# jetson_nano_breakout_rev1.net
KiCad netlist of a schematic drawn in Altium Designer
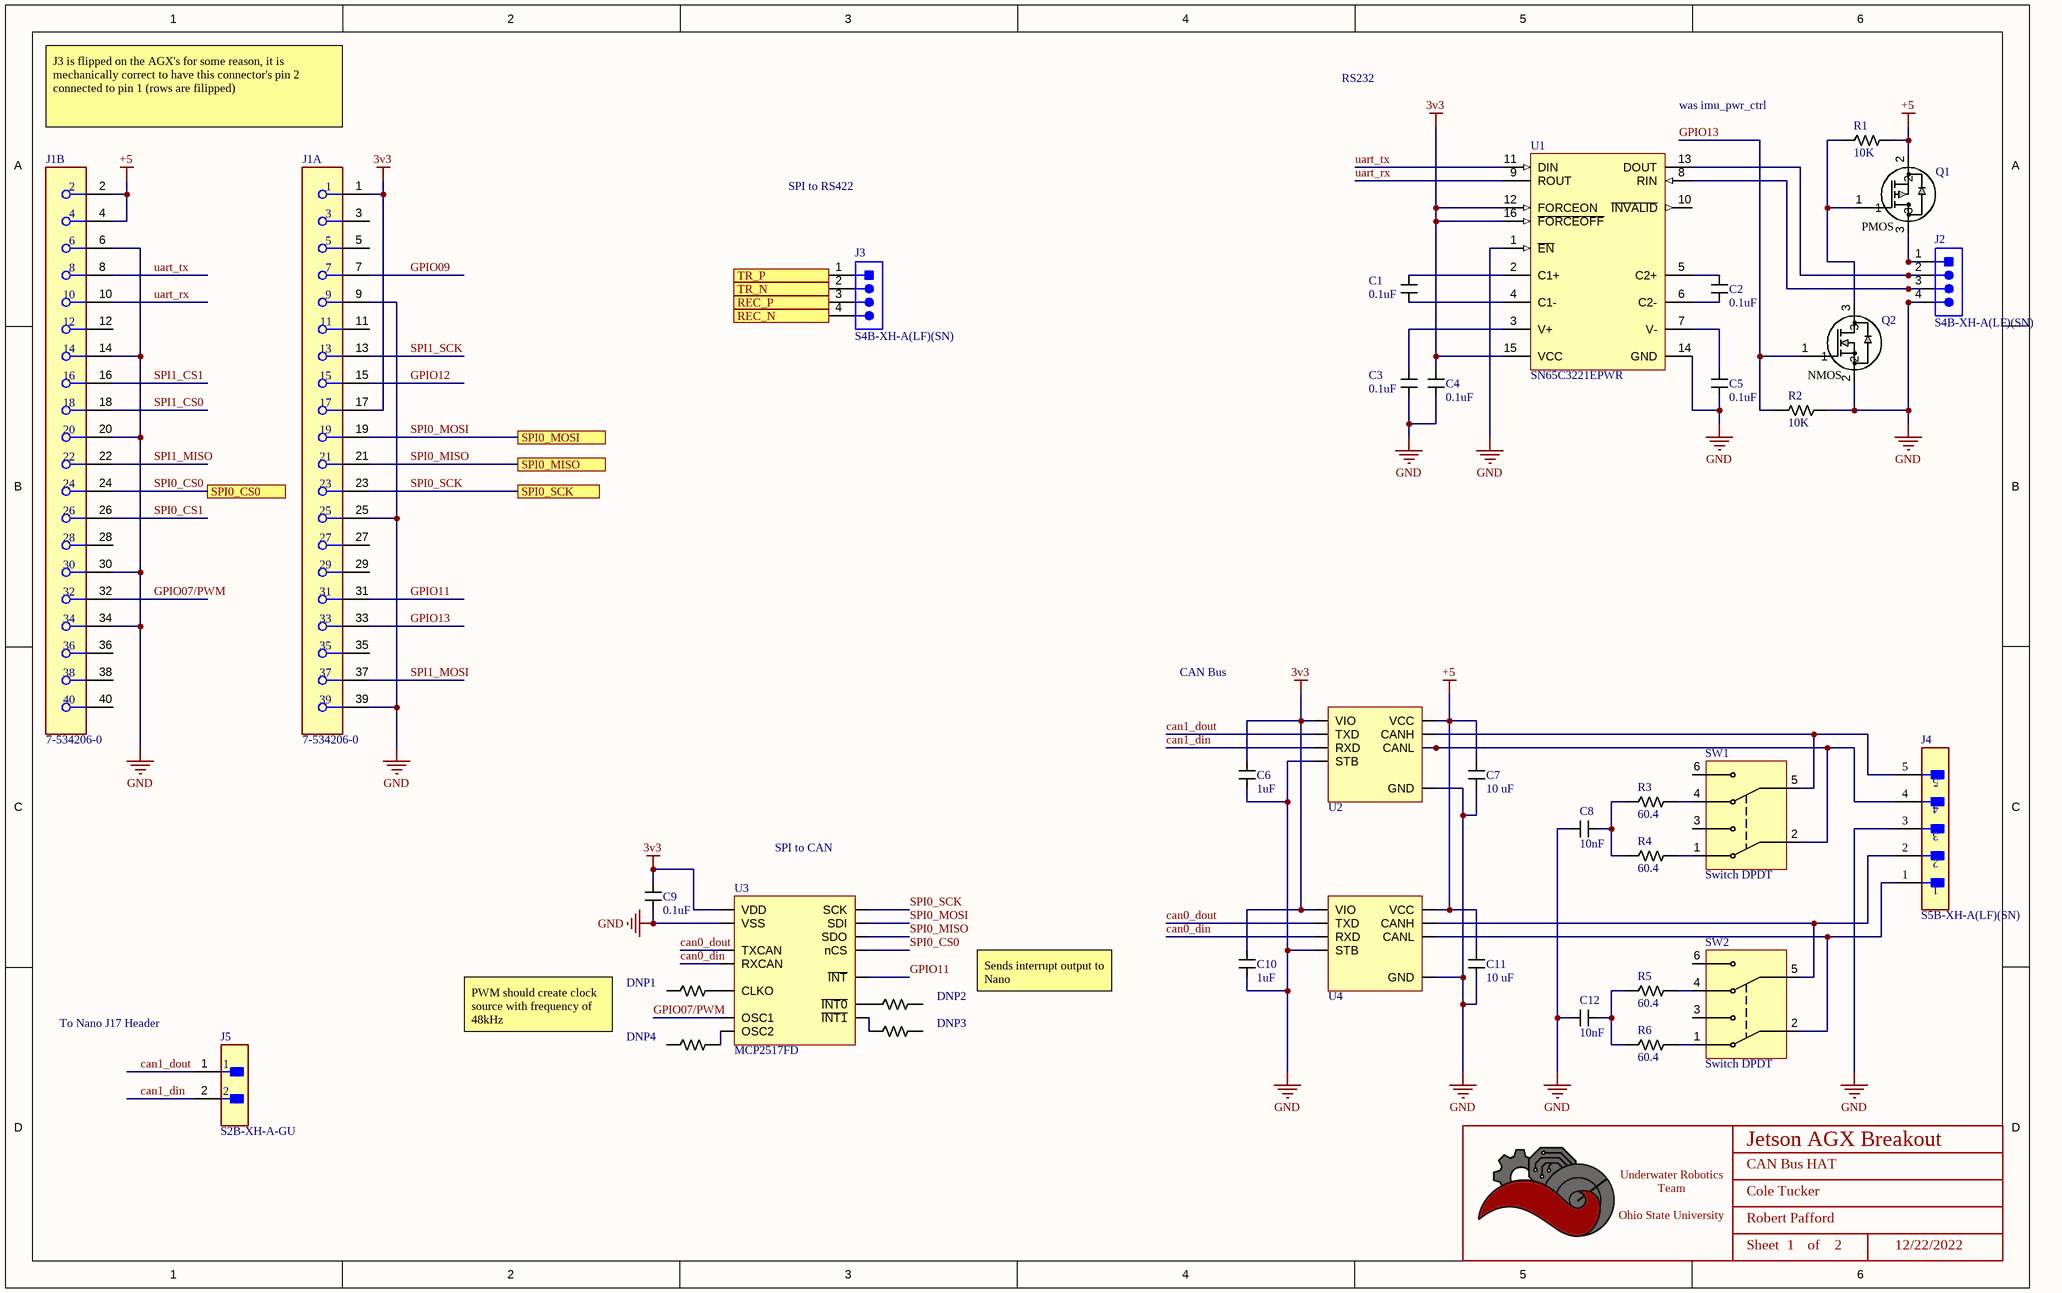
[diagram p0: jetson_nano_breakout_rev1.SchDoc]

(export (version "E")
  (design (tool "Eeschema 10.0.6"))
  (components
    (comp (ref "C1")
      (value "0.1uF")
      (footprint "CAPACITOR_0603")
      (description "Cap 100nF 6.3V +/-10%\r\nCeramic 0603")
      (fields
        (field (name "TOLERANCE") "+/- 10%")
        (field (name "VOLTAGE") "6.3V")
        (field (name "MADE BY") "Flip B")
      )
      (libsource (lib "Capacitors") (part "CAPACITOR_0.1uF_0603"))
    )
    (comp (ref "C2")
      (value "0.1uF")
      (footprint "CAPACITOR_0603")
      (description "Cap 100nF 6.3V +/-10%\r\nCeramic 0603")
      (fields
        (field (name "TOLERANCE") "+/- 10%")
        (field (name "VOLTAGE") "6.3V")
        (field (name "MADE BY") "Flip B")
      )
      (libsource (lib "Capacitors") (part "CAPACITOR_0.1uF_0603"))
    )
    (comp (ref "C3")
      (value "0.1uF")
      (footprint "CAPACITOR_0603")
      (description "Cap 100nF 6.3V +/-10%\r\nCeramic 0603")
      (fields
        (field (name "TOLERANCE") "+/- 10%")
        (field (name "VOLTAGE") "6.3V")
        (field (name "MADE BY") "Flip B")
      )
      (libsource (lib "Capacitors") (part "CAPACITOR_0.1uF_0603"))
    )
    (comp (ref "C4")
      (value "0.1uF")
      (footprint "CAPACITOR_0603")
      (description "Cap 100nF 6.3V +/-10%\r\nCeramic 0603")
      (fields
        (field (name "TOLERANCE") "+/- 10%")
        (field (name "VOLTAGE") "6.3V")
        (field (name "MADE BY") "Flip B")
      )
      (libsource (lib "Capacitors") (part "CAPACITOR_0.1uF_0603"))
    )
    (comp (ref "C5")
      (value "0.1uF")
      (footprint "CAPACITOR_0603")
      (description "Cap 100nF 6.3V +/-10%\r\nCeramic 0603")
      (fields
        (field (name "TOLERANCE") "+/- 10%")
        (field (name "VOLTAGE") "6.3V")
        (field (name "MADE BY") "Flip B")
      )
      (libsource (lib "Capacitors") (part "CAPACITOR_0.1uF_0603"))
    )
    (comp (ref "C6")
      (value "1uF")
      (footprint "CAPACITOR_0603")
      (description "Cap 1uF 16V +/-10%\r\nCeramic 0603")
      (fields
        (field (name "TOLERANCE") "+/- 10%")
        (field (name "VOLTAGE") "16V")
        (field (name "MADE BY") "Flip B")
      )
      (libsource (lib "Capacitors") (part "CAPACITOR_1uF_0603"))
    )
    (comp (ref "C7")
      (value "10uF Ceramic 6.3V")
      (footprint "CAPACITOR_0603")
      (description "Cap 10uF 6.3V +/-20%\r\nCeramic 0603")
      (fields
        (field (name "TOLERANCE") "+/- 20%")
        (field (name "VOLTAGE") "6.3V")
        (field (name "VALUE (UF)") "10 uF")
        (field (name "MADE BY") "Flip B")
      )
      (libsource (lib "Capacitors") (part "CAPACITOR_10uF_0603"))
    )
    (comp (ref "C8")
      (value "10nF")
      (footprint "CAPACITOR_0603")
      (description "Cap 10nF 6.3V +/-20%\r\nCeramic 0603")
      (fields
        (field (name "TOLERANCE") "+/- 10%")
        (field (name "VOLTAGE") "6.3V")
        (field (name "MADE BY") "Flip B")
      )
      (libsource (lib "Capacitors") (part "CAPACITOR_0.01uF_0603"))
    )
    (comp (ref "C9")
      (value "0.1uF")
      (footprint "CAPACITOR_0402")
      (description "Cap 100nF 25V +/-10%\r\nCeramic 0402")
      (fields
        (field (name "TOLERANCE") "+/- 10%")
        (field (name "VOLTAGE") "25V")
        (field (name "MADE BY") "Robert Pafford")
      )
      (libsource (lib "Capacitors") (part "CAPACITOR_0.1uF_0402"))
    )
    (comp (ref "C10")
      (value "1uF")
      (footprint "CAPACITOR_0603")
      (description "Cap 1uF 16V +/-10%\r\nCeramic 0603")
      (fields
        (field (name "TOLERANCE") "+/- 10%")
        (field (name "VOLTAGE") "16V")
        (field (name "MADE BY") "Flip B")
      )
      (libsource (lib "Capacitors") (part "CAPACITOR_1uF_0603"))
    )
    (comp (ref "C11")
      (value "10uF Ceramic 6.3V")
      (footprint "CAPACITOR_0603")
      (description "Cap 10uF 6.3V +/-20%\r\nCeramic 0603")
      (fields
        (field (name "TOLERANCE") "+/- 20%")
        (field (name "VOLTAGE") "6.3V")
        (field (name "VALUE (UF)") "10 uF")
        (field (name "MADE BY") "Flip B")
      )
      (libsource (lib "Capacitors") (part "CAPACITOR_10uF_0603"))
    )
    (comp (ref "C12")
      (value "10nF")
      (footprint "CAPACITOR_0603")
      (description "Cap 10nF 6.3V +/-20%\r\nCeramic 0603")
      (fields
        (field (name "TOLERANCE") "+/- 10%")
        (field (name "VOLTAGE") "6.3V")
        (field (name "MADE BY") "Flip B")
      )
      (libsource (lib "Capacitors") (part "CAPACITOR_0.01uF_0603"))
    )
    (comp (ref "DNP1")
      (value "DNP")
      (footprint "RESISTOR_0402")
      (description "Do Not Populate 0402")
      (libsource (lib "Resistors") (part "DNP_0402"))
    )
    (comp (ref "DNP2")
      (value "DNP")
      (footprint "RESISTOR_0402")
      (description "Do Not Populate 0402")
      (libsource (lib "Resistors") (part "DNP_0402"))
    )
    (comp (ref "DNP3")
      (value "DNP")
      (footprint "RESISTOR_0402")
      (description "Do Not Populate 0402")
      (libsource (lib "Resistors") (part "DNP_0402"))
    )
    (comp (ref "DNP4")
      (value "DNP")
      (footprint "RESISTOR_0402")
      (description "Do Not Populate 0402")
      (libsource (lib "Resistors") (part "DNP_0402"))
    )
    (comp (ref "J1")
      (value "7-534206-0")
      (footprint "FP-7-534206-0-MFG")
      (description "CONN RCPT 40POS 0.1 GOLD PCB")
      (fields
        (field (name "MANUFACTURER") "TE Connectivity")
        (field (name "OCTOPART") "https://octopart.com/7-534206-0-te+connectivity-39516831")
      )
      (libsource (lib "Altium Content Vault") (part "7acf1c4a8db21028d11741a46a6ec78"))
    )
    (comp (ref "J2")
      (value "S4B-XH-A(LF)(SN)")
      (footprint "JST-S4B-XH-A(LF)(SN)_V")
      (libsource (lib "Altium Content Vault") (part "CN-1P-M-R4"))
    )
    (comp (ref "J3")
      (value "S4B-XH-A(LF)(SN)")
      (footprint "JST-S4B-XH-A(LF)(SN)_V")
      (libsource (lib "Altium Content Vault") (part "CN-1P-M-R4"))
    )
    (comp (ref "J4")
      (value "S5B-XH-A(LF)(SN)")
      (footprint "FP-S5B-XH-A_LF_SN-MFG")
      (description "CONN HEADER R/A 5POS 2.5MM")
      (libsource (lib "Altium Content Vault") (part "bf93c07fd2649a848d0ec8585582aab"))
    )
    (comp (ref "J5")
      (value "S2B-XH-A-GU")
      (footprint "FP-S2B-XH-A-GU-MFG")
      (description "Conn Shrouded Header HDR 2 POS 2.45mm Solder ST Top Entry Thru-Hole")
      (libsource (lib "Altium Content Vault") (part "3bc925449376181038e59eaffc5286c"))
    )
    (comp (ref "Q1")
      (value "MOSFET P-CHANNEL 20V 4.7A SOT23")
      (footprint "SOT-23-3")
      (description "P-Channel 20 V 4.7A (Tc) 1.56W (Tc) Surface Mount SOT-23")
      (fields
        (field (name "MANUFACTURER_PART_NUMBER") "TSM500P02CX")
        (field (name "CREATED BY") "Robert Pafford")
      )
      (libsource (lib "Transistors") (part "TSM500P02CX"))
    )
    (comp (ref "Q2")
      (value "MOSFET N-CH 30V 5.8A SOT-23-3")
      (footprint "SOT-23-3")
      (description "N-Channel 30 V 5.8A (Ta) 1.4W (Ta) Surface Mount SOT-23-3")
      (fields (field (name "MANUFACTURER _PART_NUMBER") "AO3404A") (field (name "CREATED BY") "Dylan T"))
      (libsource (lib "Transistors") (part "AO3404A"))
    )
    (comp (ref "R1")
      (value "10k Ohm 5% 1/10W")
      (footprint "RESISTOR_0603")
      (description "RES 10k OHM 5% 1/10W 0603")
      (fields
        (field (name "TOLERANCE") "+/- 5%")
        (field (name "VALUE  (OHMS)") "10K")
        (field (name "MADE BY") "Robert Pafford")
      )
      (libsource (lib "Resistors") (part "RESISTOR_10K_0603"))
    )
    (comp (ref "R2")
      (value "10k Ohm 5% 1/10W")
      (footprint "RESISTOR_0603")
      (description "RES 10k OHM 5% 1/10W 0603")
      (fields
        (field (name "TOLERANCE") "+/- 5%")
        (field (name "VALUE  (OHMS)") "10K")
        (field (name "MADE BY") "Robert Pafford")
      )
      (libsource (lib "Resistors") (part "RESISTOR_10K_0603"))
    )
    (comp (ref "R3")
      (value "60.4 Ohm 1% 1/16W")
      (footprint "RESISTOR_0402")
      (description "RES 60.4 OHM 1% 1/16W 0402")
      (fields
        (field (name "TOLERANCE") "+/- 1%")
        (field (name "VALUE  (OHMS)") "60.4")
        (field (name "MADE BY") "Robert Pafford")
      )
      (libsource (lib "Resistors") (part "RESISTOR_60.4_0402"))
    )
    (comp (ref "R4")
      (value "60.4 Ohm 1% 1/16W")
      (footprint "RESISTOR_0402")
      (description "RES 60.4 OHM 1% 1/16W 0402")
      (fields
        (field (name "TOLERANCE") "+/- 1%")
        (field (name "VALUE  (OHMS)") "60.4")
        (field (name "MADE BY") "Robert Pafford")
      )
      (libsource (lib "Resistors") (part "RESISTOR_60.4_0402"))
    )
    (comp (ref "R5")
      (value "60.4 Ohm 1% 1/16W")
      (footprint "RESISTOR_0402")
      (description "RES 60.4 OHM 1% 1/16W 0402")
      (fields
        (field (name "TOLERANCE") "+/- 1%")
        (field (name "VALUE  (OHMS)") "60.4")
        (field (name "MADE BY") "Robert Pafford")
      )
      (libsource (lib "Resistors") (part "RESISTOR_60.4_0402"))
    )
    (comp (ref "R6")
      (value "60.4 Ohm 1% 1/16W")
      (footprint "RESISTOR_0402")
      (description "RES 60.4 OHM 1% 1/16W 0402")
      (fields
        (field (name "TOLERANCE") "+/- 1%")
        (field (name "VALUE  (OHMS)") "60.4")
        (field (name "MADE BY") "Robert Pafford")
      )
      (libsource (lib "Resistors") (part "RESISTOR_60.4_0402"))
    )
    (comp (ref "SW1")
      (value "Switch DPDT")
      (footprint "CAS-220TA")
      (description "GOLD SWITCH FLUSH SLIDE DPDT 100MA 6V")
      (fields (field (name "MADE BY") "Robert Pafford"))
      (libsource (lib "Switches") (part "CAS-220TA_CAN_TERM"))
    )
    (comp (ref "SW2")
      (value "Switch DPDT")
      (footprint "CAS-220TA")
      (description "GOLD SWITCH FLUSH SLIDE DPDT 100MA 6V")
      (fields (field (name "MADE BY") "Robert Pafford"))
      (libsource (lib "Switches") (part "CAS-220TA_CAN_TERM"))
    )
    (comp (ref "U1")
      (value "SN65C3221EPWR")
      (footprint "PW0016A_M")
      (libsource (lib "Altium Content Vault") (part "TI-SN65C3221E-TSSOP_PW-16"))
    )
    (comp (ref "U2")
      (value "CAN Transceiver")
      (footprint "SOIC-8")
      (description "CAN Interface IC High-Speed CAN Transceiver with Standby Mode")
      (fields (field (name "MADE BY") "Robert Pafford"))
      (libsource (lib "Integrated Circuits") (part "TJA1442AT"))
    )
    (comp (ref "U3")
      (value "MCP2517FD")
      (footprint "SOIC-14")
      (description "CANbus Controller CAN 2.0 SPI Interface 14-SOIC")
      (fields (field (name "MADE BY") "Robert Pafford"))
      (libsource (lib "Integrated Circuits") (part "MCP2517FD"))
    )
    (comp (ref "U4")
      (value "CAN Transceiver")
      (footprint "SOIC-8")
      (description "CAN Interface IC High-Speed CAN Transceiver with Standby Mode")
      (fields (field (name "MADE BY") "Robert Pafford"))
      (libsource (lib "Integrated Circuits") (part "TJA1442AT"))
    )
  )
  (nets
    (net (code "1") (name "+5") (class "Default")
      (node (ref "C11") (pin "1") (pinfunction "1_1") (pintype "passive"))
      (node (ref "C7") (pin "1") (pinfunction "1_1") (pintype "passive"))
      (node (ref "J1") (pin "2") (pinfunction "2_2") (pintype "passive"))
      (node (ref "J1") (pin "4") (pinfunction "4_4") (pintype "passive"))
      (node (ref "Q1") (pin "2") (pinfunction "2_2") (pintype "passive"))
      (node (ref "R1") (pin "1") (pinfunction "1_1") (pintype "passive"))
      (node (ref "U2") (pin "3") (pinfunction "VCC_3") (pintype "passive"))
      (node (ref "U4") (pin "3") (pinfunction "VCC_3") (pintype "passive"))
    )
    (net (code "2") (name "/GPIO07{slash}PWM") (class "Default")
      (node (ref "J1") (pin "32") (pinfunction "32_32") (pintype "passive"))
      (node (ref "U3") (pin "6") (pinfunction "OSC1_6") (pintype "passive"))
    )
    (net (code "3") (name "/GPIO09") (class "Default")
      (node (ref "J1") (pin "7") (pinfunction "7_7") (pintype "passive"))
    )
    (net (code "4") (name "/GPIO11") (class "Default")
      (node (ref "J1") (pin "31") (pinfunction "31_31") (pintype "passive"))
      (node (ref "U3") (pin "4") (pinfunction "~{INT}_4") (pintype "passive"))
    )
    (net (code "5") (name "/GPIO12") (class "Default")
      (node (ref "J1") (pin "15") (pinfunction "15_15") (pintype "passive"))
    )
    (net (code "6") (name "/GPIO13") (class "Default")
      (node (ref "J1") (pin "33") (pinfunction "33_33") (pintype "passive"))
      (node (ref "Q2") (pin "1") (pinfunction "1_1") (pintype "passive"))
      (node (ref "R2") (pin "1") (pinfunction "1_1") (pintype "passive"))
    )
    (net (code "7") (name "/REC_N") (class "Default")
      (node (ref "J3") (pin "4") (pinfunction "4_4") (pintype "passive"))
    )
    (net (code "8") (name "/REC_P") (class "Default")
      (node (ref "J3") (pin "3") (pinfunction "3_3") (pintype "passive"))
    )
    (net (code "9") (name "/SPI0_CS0") (class "Default")
      (node (ref "J1") (pin "24") (pinfunction "24_24") (pintype "passive"))
      (node (ref "U3") (pin "13") (pinfunction "nCS_13") (pintype "passive"))
    )
    (net (code "10") (name "/SPI0_CS1") (class "Default")
      (node (ref "J1") (pin "26") (pinfunction "26_26") (pintype "passive"))
    )
    (net (code "11") (name "/SPI0_MISO") (class "Default")
      (node (ref "J1") (pin "21") (pinfunction "21_21") (pintype "passive"))
      (node (ref "U3") (pin "12") (pinfunction "SDO_12") (pintype "passive"))
    )
    (net (code "12") (name "/SPI0_MOSI") (class "Default")
      (node (ref "J1") (pin "19") (pinfunction "19_19") (pintype "passive"))
      (node (ref "U3") (pin "11") (pinfunction "SDI_11") (pintype "passive"))
    )
    (net (code "13") (name "/SPI0_SCK") (class "Default")
      (node (ref "J1") (pin "23") (pinfunction "23_23") (pintype "passive"))
      (node (ref "U3") (pin "10") (pinfunction "SCK_10") (pintype "passive"))
    )
    (net (code "14") (name "/SPI1_CS0") (class "Default")
      (node (ref "J1") (pin "18") (pinfunction "18_18") (pintype "passive"))
    )
    (net (code "15") (name "/SPI1_CS1") (class "Default")
      (node (ref "J1") (pin "16") (pinfunction "16_16") (pintype "passive"))
    )
    (net (code "16") (name "/SPI1_MISO") (class "Default")
      (node (ref "J1") (pin "22") (pinfunction "22_22") (pintype "passive"))
    )
    (net (code "17") (name "/SPI1_MOSI") (class "Default")
      (node (ref "J1") (pin "37") (pinfunction "37_37") (pintype "passive"))
    )
    (net (code "18") (name "/SPI1_SCK") (class "Default")
      (node (ref "J1") (pin "13") (pinfunction "13_13") (pintype "passive"))
    )
    (net (code "19") (name "/TR_N") (class "Default")
      (node (ref "J3") (pin "2") (pinfunction "2_2") (pintype "passive"))
    )
    (net (code "20") (name "/TR_P") (class "Default")
      (node (ref "J3") (pin "1") (pinfunction "1_1") (pintype "passive"))
    )
    (net (code "21") (name "/can0_din") (class "Default")
      (node (ref "U3") (pin "2") (pinfunction "RXCAN_2") (pintype "passive"))
      (node (ref "U4") (pin "4") (pinfunction "RXD_4") (pintype "passive"))
    )
    (net (code "22") (name "/can0_dout") (class "Default")
      (node (ref "U3") (pin "1") (pinfunction "TXCAN_1") (pintype "passive"))
      (node (ref "U4") (pin "1") (pinfunction "TXD_1") (pintype "passive"))
    )
    (net (code "23") (name "/can1_din") (class "Default")
      (node (ref "J5") (pin "2") (pinfunction "2_2") (pintype "passive"))
      (node (ref "U2") (pin "4") (pinfunction "RXD_4") (pintype "passive"))
    )
    (net (code "24") (name "/can1_dout") (class "Default")
      (node (ref "J5") (pin "1") (pinfunction "1_1") (pintype "passive"))
      (node (ref "U2") (pin "1") (pinfunction "TXD_1") (pintype "passive"))
    )
    (net (code "25") (name "/uart_rx") (class "Default")
      (node (ref "J1") (pin "10") (pinfunction "10_10") (pintype "passive"))
      (node (ref "U1") (pin "9") (pinfunction "ROUT_9") (pintype "tri_state"))
    )
    (net (code "26") (name "/uart_tx") (class "Default")
      (node (ref "J1") (pin "8") (pinfunction "8_8") (pintype "passive"))
      (node (ref "U1") (pin "11") (pinfunction "DIN_11") (pintype "input"))
    )
    (net (code "27") (name "3v3") (class "Default")
      (node (ref "C10") (pin "1") (pinfunction "1_1") (pintype "passive"))
      (node (ref "C4") (pin "1") (pinfunction "1_1") (pintype "passive"))
      (node (ref "C6") (pin "1") (pinfunction "1_1") (pintype "passive"))
      (node (ref "C9") (pin "1") (pinfunction "1_1") (pintype "passive"))
      (node (ref "J1") (pin "1") (pinfunction "1_1") (pintype "passive"))
      (node (ref "J1") (pin "17") (pinfunction "17_17") (pintype "passive"))
      (node (ref "U1") (pin "12") (pinfunction "FORCEON_12") (pintype "input"))
      (node (ref "U1") (pin "15") (pinfunction "VCC_15") (pintype "power_in"))
      (node (ref "U1") (pin "16") (pinfunction "~{FORCEOFF}_16") (pintype "input"))
      (node (ref "U2") (pin "5") (pinfunction "VIO_5") (pintype "passive"))
      (node (ref "U3") (pin "14") (pinfunction "VDD_14") (pintype "passive"))
      (node (ref "U4") (pin "5") (pinfunction "VIO_5") (pintype "passive"))
    )
    (net (code "28") (name "GND") (class "Default")
      (node (ref "C10") (pin "2") (pinfunction "2_2") (pintype "passive"))
      (node (ref "C11") (pin "2") (pinfunction "2_2") (pintype "passive"))
      (node (ref "C12") (pin "1") (pinfunction "1_1") (pintype "passive"))
      (node (ref "C3") (pin "2") (pinfunction "2_2") (pintype "passive"))
      (node (ref "C4") (pin "2") (pinfunction "2_2") (pintype "passive"))
      (node (ref "C5") (pin "2") (pinfunction "2_2") (pintype "passive"))
      (node (ref "C6") (pin "2") (pinfunction "2_2") (pintype "passive"))
      (node (ref "C7") (pin "2") (pinfunction "2_2") (pintype "passive"))
      (node (ref "C8") (pin "1") (pinfunction "1_1") (pintype "passive"))
      (node (ref "C9") (pin "2") (pinfunction "2_2") (pintype "passive"))
      (node (ref "J1") (pin "14") (pinfunction "14_14") (pintype "passive"))
      (node (ref "J1") (pin "20") (pinfunction "20_20") (pintype "passive"))
      (node (ref "J1") (pin "25") (pinfunction "25_25") (pintype "passive"))
      (node (ref "J1") (pin "30") (pinfunction "30_30") (pintype "passive"))
      (node (ref "J1") (pin "34") (pinfunction "34_34") (pintype "passive"))
      (node (ref "J1") (pin "39") (pinfunction "39_39") (pintype "passive"))
      (node (ref "J1") (pin "6") (pinfunction "6_6") (pintype "passive"))
      (node (ref "J1") (pin "9") (pinfunction "9_9") (pintype "passive"))
      (node (ref "J2") (pin "4") (pinfunction "4_4") (pintype "passive"))
      (node (ref "J4") (pin "3") (pinfunction "3_3") (pintype "passive"))
      (node (ref "Q2") (pin "2") (pinfunction "2_2") (pintype "passive"))
      (node (ref "R2") (pin "2") (pinfunction "2_2") (pintype "passive"))
      (node (ref "U1") (pin "1") (pinfunction "~{EN}_1") (pintype "input"))
      (node (ref "U1") (pin "14") (pinfunction "GND_14") (pintype "power_in"))
      (node (ref "U2") (pin "2") (pinfunction "GND_2") (pintype "passive"))
      (node (ref "U2") (pin "8") (pinfunction "STB_8") (pintype "passive"))
      (node (ref "U3") (pin "7") (pinfunction "VSS_7") (pintype "passive"))
      (node (ref "U4") (pin "2") (pinfunction "GND_2") (pintype "passive"))
      (node (ref "U4") (pin "8") (pinfunction "STB_8") (pintype "passive"))
    )
    (net (code "29") (name "Net-(C8-Pad2)") (class "Default")
      (node (ref "C8") (pin "2") (pinfunction "2_2") (pintype "passive"))
      (node (ref "R3") (pin "2") (pinfunction "2_2") (pintype "passive"))
      (node (ref "R4") (pin "2") (pinfunction "2_2") (pintype "passive"))
    )
    (net (code "30") (name "Net-(C12-Pad2)") (class "Default")
      (node (ref "C12") (pin "2") (pinfunction "2_2") (pintype "passive"))
      (node (ref "R5") (pin "2") (pinfunction "2_2") (pintype "passive"))
      (node (ref "R6") (pin "2") (pinfunction "2_2") (pintype "passive"))
    )
    (net (code "31") (name "Net-(J2-Pad1)") (class "Default")
      (node (ref "J2") (pin "1") (pinfunction "1_1") (pintype "passive"))
      (node (ref "Q1") (pin "3") (pinfunction "3_3") (pintype "passive"))
    )
    (net (code "32") (name "Net-(Q1-Pad1)") (class "Default")
      (node (ref "Q1") (pin "1") (pinfunction "1_1") (pintype "passive"))
      (node (ref "Q2") (pin "3") (pinfunction "3_3") (pintype "passive"))
      (node (ref "R1") (pin "2") (pinfunction "2_2") (pintype "passive"))
    )
    (net (code "33") (name "Net-(R3-Pad1)") (class "Default")
      (node (ref "R3") (pin "1") (pinfunction "1_1") (pintype "passive"))
      (node (ref "SW1") (pin "4") (pintype "passive"))
    )
    (net (code "34") (name "Net-(R4-Pad1)") (class "Default")
      (node (ref "R4") (pin "1") (pinfunction "1_1") (pintype "passive"))
      (node (ref "SW1") (pin "1") (pintype "passive"))
    )
    (net (code "35") (name "Net-(R5-Pad1)") (class "Default")
      (node (ref "R5") (pin "1") (pinfunction "1_1") (pintype "passive"))
      (node (ref "SW2") (pin "4") (pintype "passive"))
    )
    (net (code "36") (name "Net-(R6-Pad1)") (class "Default")
      (node (ref "R6") (pin "1") (pinfunction "1_1") (pintype "passive"))
      (node (ref "SW2") (pin "1") (pintype "passive"))
    )
    (net (code "37") (name "Net-(U1-C1+)") (class "Default")
      (node (ref "C1") (pin "1") (pinfunction "1_1") (pintype "passive"))
      (node (ref "U1") (pin "2") (pinfunction "C1+_2") (pintype "passive"))
    )
    (net (code "38") (name "Net-(U1-C1-)") (class "Default")
      (node (ref "C1") (pin "2") (pinfunction "2_2") (pintype "passive"))
      (node (ref "U1") (pin "4") (pinfunction "C1-_4") (pintype "passive"))
    )
    (net (code "39") (name "Net-(U1-C2+)") (class "Default")
      (node (ref "C2") (pin "1") (pinfunction "1_1") (pintype "passive"))
      (node (ref "U1") (pin "5") (pinfunction "C2+_5") (pintype "passive"))
    )
    (net (code "40") (name "Net-(U1-C2-)") (class "Default")
      (node (ref "C2") (pin "2") (pinfunction "2_2") (pintype "passive"))
      (node (ref "U1") (pin "6") (pinfunction "C2-_6") (pintype "passive"))
    )
    (net (code "41") (name "Net-(U1-DOUT)") (class "Default")
      (node (ref "J2") (pin "2") (pinfunction "2_2") (pintype "passive"))
      (node (ref "U1") (pin "13") (pinfunction "DOUT_13") (pintype "tri_state"))
    )
    (net (code "42") (name "Net-(U1-RIN)") (class "Default")
      (node (ref "J2") (pin "3") (pinfunction "3_3") (pintype "passive"))
      (node (ref "U1") (pin "8") (pinfunction "RIN_8") (pintype "input"))
    )
    (net (code "43") (name "Net-(U1-V+)") (class "Default")
      (node (ref "C3") (pin "1") (pinfunction "1_1") (pintype "passive"))
      (node (ref "U1") (pin "3") (pinfunction "V+_3") (pintype "power_in"))
    )
    (net (code "44") (name "Net-(U1-V-)") (class "Default")
      (node (ref "C5") (pin "1") (pinfunction "1_1") (pintype "passive"))
      (node (ref "U1") (pin "7") (pinfunction "V-_7") (pintype "power_in"))
    )
    (net (code "45") (name "Net-(U2-CANH)") (class "Default")
      (node (ref "J4") (pin "5") (pinfunction "5_5") (pintype "passive"))
      (node (ref "SW1") (pin "5") (pintype "passive"))
      (node (ref "U2") (pin "7") (pinfunction "CANH_7") (pintype "passive"))
    )
    (net (code "46") (name "Net-(U2-CANL)") (class "Default")
      (node (ref "J4") (pin "4") (pinfunction "4_4") (pintype "passive"))
      (node (ref "SW1") (pin "2") (pintype "passive"))
      (node (ref "U2") (pin "6") (pinfunction "CANL_6") (pintype "passive"))
    )
    (net (code "47") (name "Net-(U3-CLKO)") (class "Default")
      (node (ref "DNP1") (pin "1") (pinfunction "1_1") (pintype "passive"))
      (node (ref "U3") (pin "3") (pinfunction "CLKO_3") (pintype "passive"))
    )
    (net (code "48") (name "Net-(U3-OSC2)") (class "Default")
      (node (ref "DNP4") (pin "1") (pinfunction "1_1") (pintype "passive"))
      (node (ref "U3") (pin "5") (pinfunction "OSC2_5") (pintype "passive"))
    )
    (net (code "49") (name "Net-(U3-~{INT0})") (class "Default")
      (node (ref "DNP2") (pin "2") (pinfunction "2_2") (pintype "passive"))
      (node (ref "U3") (pin "9") (pinfunction "~{INT0}_9") (pintype "passive"))
    )
    (net (code "50") (name "Net-(U3-~{INT1})") (class "Default")
      (node (ref "DNP3") (pin "2") (pinfunction "2_2") (pintype "passive"))
      (node (ref "U3") (pin "8") (pinfunction "~{INT1}_8") (pintype "passive"))
    )
    (net (code "51") (name "Net-(U4-CANH)") (class "Default")
      (node (ref "J4") (pin "2") (pinfunction "2_2") (pintype "passive"))
      (node (ref "SW2") (pin "5") (pintype "passive"))
      (node (ref "U4") (pin "7") (pinfunction "CANH_7") (pintype "passive"))
    )
    (net (code "52") (name "Net-(U4-CANL)") (class "Default")
      (node (ref "J4") (pin "1") (pinfunction "1_1") (pintype "passive"))
      (node (ref "SW2") (pin "2") (pintype "passive"))
      (node (ref "U4") (pin "6") (pinfunction "CANL_6") (pintype "passive"))
    )
    (net (code "53") (name "unconnected-(DNP1-Pad2)") (class "Default")
      (node (ref "DNP1") (pin "2") (pinfunction "2_2") (pintype "passive"))
    )
    (net (code "54") (name "unconnected-(DNP2-Pad1)") (class "Default")
      (node (ref "DNP2") (pin "1") (pinfunction "1_1") (pintype "passive"))
    )
    (net (code "55") (name "unconnected-(DNP3-Pad1)") (class "Default")
      (node (ref "DNP3") (pin "1") (pinfunction "1_1") (pintype "passive"))
    )
    (net (code "56") (name "unconnected-(DNP4-Pad2)") (class "Default")
      (node (ref "DNP4") (pin "2") (pinfunction "2_2") (pintype "passive"))
    )
    (net (code "57") (name "unconnected-(J1-Pad3)") (class "Default")
      (node (ref "J1") (pin "3") (pinfunction "3_3") (pintype "passive"))
    )
    (net (code "58") (name "unconnected-(J1-Pad5)") (class "Default")
      (node (ref "J1") (pin "5") (pinfunction "5_5") (pintype "passive"))
    )
    (net (code "59") (name "unconnected-(J1-Pad11)") (class "Default")
      (node (ref "J1") (pin "11") (pinfunction "11_11") (pintype "passive"))
    )
    (net (code "60") (name "unconnected-(J1-Pad12)") (class "Default")
      (node (ref "J1") (pin "12") (pinfunction "12_12") (pintype "passive"))
    )
    (net (code "61") (name "unconnected-(J1-Pad27)") (class "Default")
      (node (ref "J1") (pin "27") (pinfunction "27_27") (pintype "passive"))
    )
    (net (code "62") (name "unconnected-(J1-Pad28)") (class "Default")
      (node (ref "J1") (pin "28") (pinfunction "28_28") (pintype "passive"))
    )
    (net (code "63") (name "unconnected-(J1-Pad29)") (class "Default")
      (node (ref "J1") (pin "29") (pinfunction "29_29") (pintype "passive"))
    )
    (net (code "64") (name "unconnected-(J1-Pad35)") (class "Default")
      (node (ref "J1") (pin "35") (pinfunction "35_35") (pintype "passive"))
    )
    (net (code "65") (name "unconnected-(J1-Pad36)") (class "Default")
      (node (ref "J1") (pin "36") (pinfunction "36_36") (pintype "passive"))
    )
    (net (code "66") (name "unconnected-(J1-Pad38)") (class "Default")
      (node (ref "J1") (pin "38") (pinfunction "38_38") (pintype "passive"))
    )
    (net (code "67") (name "unconnected-(J1-Pad40)") (class "Default")
      (node (ref "J1") (pin "40") (pinfunction "40_40") (pintype "passive"))
    )
    (net (code "68") (name "unconnected-(SW1-Pad3)") (class "Default")
      (node (ref "SW1") (pin "3") (pintype "passive"))
    )
    (net (code "69") (name "unconnected-(SW1-Pad6)") (class "Default")
      (node (ref "SW1") (pin "6") (pintype "passive"))
    )
    (net (code "70") (name "unconnected-(SW2-Pad3)") (class "Default")
      (node (ref "SW2") (pin "3") (pintype "passive"))
    )
    (net (code "71") (name "unconnected-(SW2-Pad6)") (class "Default")
      (node (ref "SW2") (pin "6") (pintype "passive"))
    )
    (net (code "72") (name "unconnected-(U1-~{INVALID}-Pad10)") (class "Default")
      (node (ref "U1") (pin "10") (pinfunction "~{INVALID}_10") (pintype "output"))
    )
  )
)
